# BT100_V1_1.net
KiCad netlist of a schematic drawn in Altium Designer
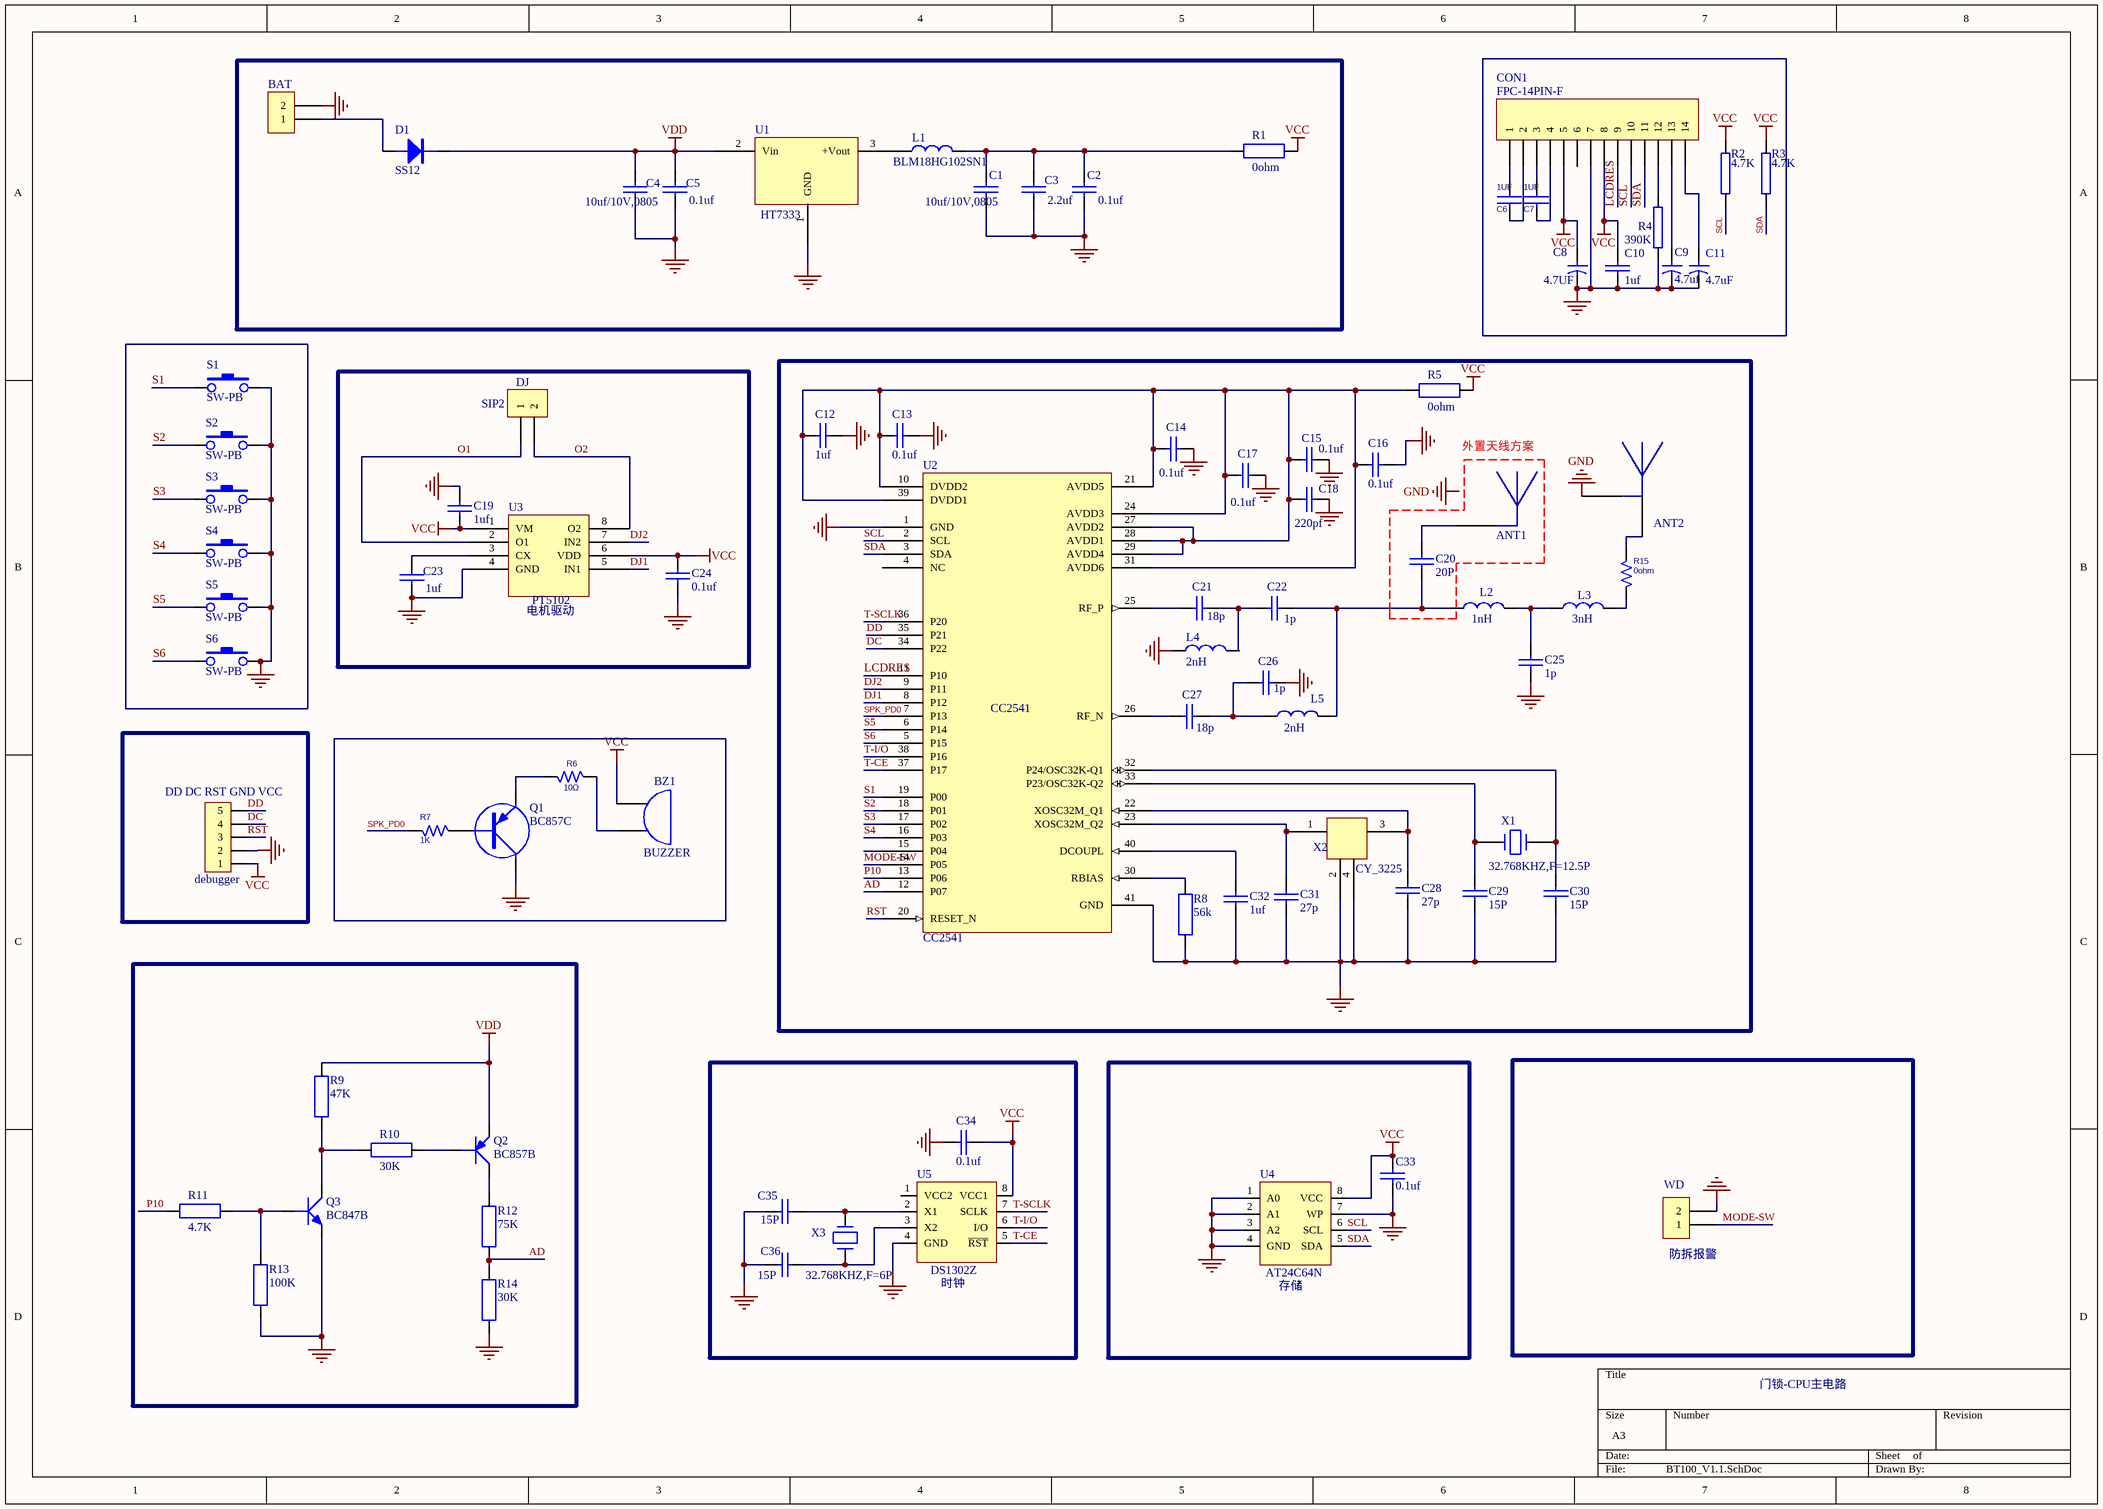
[diagram p0: BT100_V1.1.SchDoc]

(export (version "E")
  (design (tool "Eeschema 10.0.6"))
  (components
    (comp (ref "ANT1") (value "ANT") (footprint "IPEX") (libsource (lib "BT100_Project") (part "ANT1")))
    (comp (ref "ANT2") (value "ANT") (footprint "ANT") (libsource (lib "BT100_Project") (part "ANT")))
    (comp (ref "BAT")
      (value "CN1")
      (footprint "2PAD-9")
      (description "Connector")
      (libsource (lib "") (part "CON2_1"))
    )
    (comp (ref "BZ1")
      (value "BUZZER")
      (footprint "2PAD-9")
      (description "Buzzer")
      (libsource (lib "LG_SCH") (part "BUZZER"))
    )
    (comp (ref "C1")
      (value "10uf/10V,0805")
      (footprint "门锁:PC5-*****-**-0A_0805_TDK")
      (description "PC7-*****-KQA0A")
      (libsource (lib "Schlib") (part "PC7_0402_YAGEO"))
    )
    (comp (ref "C2")
      (value "0.1uf")
      (footprint "门锁:PC5-*****-**-0A_0603_TDK")
      (description "PC7-*****-KQA0A")
      (libsource (lib "Schlib") (part "PC7_0402_YAGEO"))
    )
    (comp (ref "C3")
      (value "2.2uf")
      (footprint "门锁:PC5-*****-**-0A_0603_TDK")
      (description "PC7-*****-KQA0A")
      (libsource (lib "Schlib") (part "PC7_0402_YAGEO"))
    )
    (comp (ref "C4")
      (value "10uf/10V,0805")
      (footprint "门锁:PC5-*****-**-0A_0805_TDK")
      (description "PC7-*****-KQA0A")
      (libsource (lib "Schlib") (part "PC7_0402_YAGEO"))
    )
    (comp (ref "C5")
      (value "0.1uf")
      (footprint "门锁:PC5-*****-**-0A_0603_TDK")
      (description "PC7-*****-KQA0A")
      (libsource (lib "Schlib") (part "PC7_0402_YAGEO"))
    )
    (comp (ref "C6") (value "1UF") (footprint "0603") (libsource (lib "*") (part "CAP NP_Dup3")))
    (comp (ref "C7") (value "1UF") (footprint "0603") (libsource (lib "*") (part "CAP NP_Dup3")))
    (comp (ref "C8")
      (value "4.7UF")
      (footprint "3216C")
      (description "1206")
      (libsource (lib "*") (part "CAP_E"))
    )
    (comp (ref "C9")
      (value "4.7uf")
      (footprint "3216C")
      (description "1206")
      (libsource (lib "*") (part "CAP_E"))
    )
    (comp (ref "C10")
      (value "1uf")
      (footprint "0603")
      (description "Capacitor")
      (libsource (lib "*") (part "CAP"))
    )
    (comp (ref "C11")
      (value "4.7uF")
      (footprint "3216C")
      (description "1206")
      (libsource (lib "*") (part "CAP_E"))
    )
    (comp (ref "C12")
      (value "1uf")
      (footprint "PC5-*****-**-0A_0603_TDK")
      (description "PC7-*****-KQA0A")
      (libsource (lib "Schlib") (part "PC7_0402_YAGEO"))
    )
    (comp (ref "C13")
      (value "0.1uf")
      (footprint "PC7-*****-KO-0A_0603_TDK")
      (description "PC7-*****-KQA0A")
      (libsource (lib "Schlib") (part "PC7_0402_YAGEO"))
    )
    (comp (ref "C14")
      (value "0.1uf")
      (footprint "PC5-*****-**-0A_0603_TDK")
      (description "PC7-*****-KQA0A")
      (libsource (lib "Schlib") (part "PC7_0402_YAGEO"))
    )
    (comp (ref "C15")
      (value "0.1uf")
      (footprint "PC7-*****-KQA0A_0402_YAGEO")
      (description "PC7-*****-KQA0A")
      (libsource (lib "Schlib") (part "PC7_0402_YAGEO"))
    )
    (comp (ref "C16")
      (value "0.1uf")
      (footprint "PC7-*****-KQA0A_0402_YAGEO")
      (description "PC7-*****-KQA0A")
      (libsource (lib "Schlib") (part "PC7_0402_YAGEO"))
    )
    (comp (ref "C17")
      (value "0.1uf")
      (footprint "PC7-*****-KQA0A_0402_YAGEO")
      (description "PC7-*****-KQA0A")
      (libsource (lib "Schlib") (part "PC7_0402_YAGEO"))
    )
    (comp (ref "C18")
      (value "220pf")
      (footprint "PC7-*****-KQA0A_0402_YAGEO")
      (description "PC7-*****-KQA0A")
      (libsource (lib "Schlib") (part "PC7_0402_YAGEO"))
    )
    (comp (ref "C19")
      (value "1uf")
      (footprint "门锁:PC5-*****-**-0A_0603_TDK")
      (description "PC7-*****-KQA0A")
      (libsource (lib "Schlib") (part "PC7_0402_YAGEO"))
    )
    (comp (ref "C20")
      (value "20P")
      (footprint "PC7-*****-KQA0A_0402_YAGEO")
      (description "PC7-*****-KQA0A")
      (libsource (lib "Schlib") (part "PC7_0402_YAGEO"))
    )
    (comp (ref "C21")
      (value "18p")
      (footprint "PC7-*****-KQA0A_0402_YAGEO")
      (description "PC7-*****-KQA0A")
      (libsource (lib "Schlib") (part "PC7_0402_YAGEO"))
    )
    (comp (ref "C22")
      (value "1p")
      (footprint "PC7-*****-KQA0A_0402_YAGEO")
      (description "PC7-*****-KQA0A")
      (libsource (lib "Schlib") (part "PC7_0402_YAGEO"))
    )
    (comp (ref "C23")
      (value "1uf")
      (footprint "门锁:PC5-*****-**-0A_0603_TDK")
      (description "PC7-*****-KQA0A")
      (libsource (lib "Schlib") (part "PC7_0402_YAGEO"))
    )
    (comp (ref "C24")
      (value "0.1uf")
      (footprint "门锁:PC5-*****-**-0A_0603_TDK")
      (description "PC7-*****-KQA0A")
      (libsource (lib "Schlib") (part "PC7_0402_YAGEO"))
    )
    (comp (ref "C25")
      (value "1p")
      (footprint "PC7-*****-KQA0A_0402_YAGEO")
      (description "PC7-*****-KQA0A")
      (libsource (lib "Schlib") (part "PC7_0402_YAGEO"))
    )
    (comp (ref "C26")
      (value "1p")
      (footprint "PC7-*****-KQA0A_0402_YAGEO")
      (description "PC7-*****-KQA0A")
      (libsource (lib "Schlib") (part "PC7_0402_YAGEO"))
    )
    (comp (ref "C27")
      (value "18p")
      (footprint "PC7-*****-KQA0A_0402_YAGEO")
      (description "PC7-*****-KQA0A")
      (libsource (lib "Schlib") (part "PC7_0402_YAGEO"))
    )
    (comp (ref "C28")
      (value "27p")
      (footprint "PC7-*****-KO-0A_0603_TDK")
      (description "PC7-*****-KQA0A")
      (libsource (lib "Schlib") (part "PC7_0402_YAGEO"))
    )
    (comp (ref "C29")
      (value "15P")
      (footprint "PC5-*****-**-0A_0603_TDK")
      (description "PC7-*****-KQA0A")
      (libsource (lib "Schlib") (part "PC7_0402_YAGEO"))
    )
    (comp (ref "C30")
      (value "15P")
      (footprint "PC7-*****-KO-0A_0603_TDK")
      (description "PC7-*****-KQA0A")
      (libsource (lib "Schlib") (part "PC7_0402_YAGEO"))
    )
    (comp (ref "C31")
      (value "27p")
      (footprint "PC7-*****-KO-0A_0603_TDK")
      (description "PC7-*****-KQA0A")
      (libsource (lib "Schlib") (part "PC7_0402_YAGEO"))
    )
    (comp (ref "C32")
      (value "1uf")
      (footprint "PC5-*****-**-0A_0603_TDK")
      (description "PC7-*****-KQA0A")
      (libsource (lib "Schlib") (part "PC7_0402_YAGEO"))
    )
    (comp (ref "C33")
      (value "0.1uf")
      (footprint "PC5-*****-**-0A_0603_TDK")
      (description "PC7-*****-KQA0A")
      (libsource (lib "Schlib") (part "PC7_0402_YAGEO"))
    )
    (comp (ref "C34")
      (value "0.1uf")
      (footprint "PC7-*****-KO-0A_0603_TDK")
      (description "PC7-*****-KQA0A")
      (libsource (lib "Schlib") (part "PC7_0402_YAGEO"))
    )
    (comp (ref "C35")
      (value "15P")
      (footprint "PC7-*****-KO-0A_0603_TDK")
      (description "PC7-*****-KQA0A")
      (libsource (lib "Schlib") (part "PC7_0402_YAGEO"))
    )
    (comp (ref "C36")
      (value "15P")
      (footprint "PC7-*****-KO-0A_0603_TDK")
      (description "PC7-*****-KQA0A")
      (libsource (lib "Schlib") (part "PC7_0402_YAGEO"))
    )
    (comp (ref "CON1")
      (value "FPC-14PIN-F")
      (footprint "FFC6214")
      (description "Connector")
      (libsource (lib "*") (part "CON14"))
    )
    (comp (ref "D1")
      (value "SS12")
      (footprint "SS12-DIDEO")
      (description "PDD-00330-00-2A")
      (libsource (lib "*") (part "PDD_SD101CWS"))
    )
    (comp (ref "DD DC RST GND VCC")
      (value "debugger")
      (footprint "ISCP-5PIN")
      (libsource (lib "BJC") (part "CON5"))
    )
    (comp (ref "DJ")
      (value "SIP2")
      (footprint "2PAD-9")
      (description "Connector")
      (libsource (lib "BJC") (part "CON2"))
    )
    (comp (ref "L1")
      (value "BLM18HG102SN1")
      (footprint "门锁:PC5-*****-**-0A_0603_TDK")
      (description "PWL-00195-00-20")
      (libsource (lib "Schlib") (part "PWL_18nH"))
    )
    (comp (ref "L2")
      (value "1nH")
      (footprint "PC5-*****-**-0A_0402_TDK")
      (description "PWL-00195-00-20")
      (libsource (lib "Schlib") (part "PWL_18nH"))
    )
    (comp (ref "L3")
      (value "3nH")
      (footprint "PC5-*****-**-0A_0402_TDK")
      (description "PWL-00195-00-20")
      (libsource (lib "Schlib") (part "PWL_18nH"))
    )
    (comp (ref "L4")
      (value "2nH")
      (footprint "PC5-*****-**-0A_0402_TDK")
      (description "PWL-00195-00-20")
      (libsource (lib "Schlib") (part "PWL_18nH"))
    )
    (comp (ref "L5")
      (value "2nH")
      (footprint "PC5-*****-**-0A_0402_TDK")
      (description "PWL-00195-00-20")
      (libsource (lib "Schlib") (part "PWL_18nH"))
    )
    (comp (ref "Q1")
      (value "BC857C")
      (footprint "PTR-C0025-00-2A_2SC1623")
      (description "PNP Transistor")
      (libsource (lib "LG_SCH") (part "PNP"))
    )
    (comp (ref "Q2")
      (value "BC857B")
      (footprint "PTR-C0025-00-2A_2SC1623")
      (libsource (lib "*") (part "PTR-PNP"))
    )
    (comp (ref "Q3")
      (value "BC847B")
      (footprint "PTR-C0025-00-2A_2SC1623")
      (description "PTR-C0028-00-2A")
      (libsource (lib "Schlib") (part "PTR_2SC3356"))
    )
    (comp (ref "R1")
      (value "0ohm")
      (footprint "门锁:PC5-*****-**-0A_0603_TDK")
      (description "PRC-*****-AM-0A_0603")
      (libsource (lib "Schlib") (part "PRC_0603"))
    )
    (comp (ref "R2") (value "4.7K") (footprint "0603") (libsource (lib "LG_SCH") (part "RES")))
    (comp (ref "R3") (value "4.7K") (footprint "0603") (libsource (lib "LG_SCH") (part "RES")))
    (comp (ref "R4") (value "390K") (footprint "0603") (libsource (lib "LG_SCH") (part "RES")))
    (comp (ref "R5")
      (value "0ohm")
      (footprint "PRC-*****-AM-0A_0603")
      (description "PRC-*****-AM-0A_0603")
      (libsource (lib "Schlib") (part "PRC_0603"))
    )
    (comp (ref "R6") (value "10Ω") (footprint "0603") (libsource (lib "*") (part "R_Dup3")))
    (comp (ref "R7") (value "1K") (footprint "0603") (libsource (lib "*") (part "R_Dup3")))
    (comp (ref "R8")
      (value "56k")
      (footprint "PRC-*****-BM-0A_0402")
      (description "PRC-*****-AM-0A_0603")
      (libsource (lib "Schlib") (part "PRC_0603"))
    )
    (comp (ref "R9")
      (value "47K")
      (footprint "门锁:PC7-*****-KO-0A_0603_TDK")
      (description "PRC-*****-AM-0A_0603")
      (libsource (lib "Schlib") (part "PRC_0603"))
    )
    (comp (ref "R10")
      (value "30K")
      (footprint "门锁:PC5-*****-**-0A_0603_TDK")
      (description "PRC-*****-AM-0A_0603")
      (libsource (lib "Schlib") (part "PRC_0603"))
    )
    (comp (ref "R11")
      (value "4.7K")
      (footprint "门锁:PC5-*****-**-0A_0603_TDK")
      (description "PRC-*****-AM-0A_0603")
      (libsource (lib "Schlib") (part "PRC_0603"))
    )
    (comp (ref "R12")
      (value "75K")
      (footprint "门锁:PC5-*****-**-0A_0603_TDK")
      (description "PRC-*****-AM-0A_0603")
      (libsource (lib "Schlib") (part "PRC_0603"))
    )
    (comp (ref "R13")
      (value "100K")
      (footprint "门锁:PC5-*****-**-0A_0603_TDK")
      (description "PRC-*****-AM-0A_0603")
      (libsource (lib "Schlib") (part "PRC_0603"))
    )
    (comp (ref "R14")
      (value "30K")
      (footprint "门锁:PC5-*****-**-0A_0603_TDK")
      (description "PRC-*****-AM-0A_0603")
      (libsource (lib "Schlib") (part "PRC_0603"))
    )
    (comp (ref "R15")
      (value "0ohm")
      (footprint "PC7-*****-KQA0A_0402_YAGEO")
      (libsource (lib "*") (part "R_Dup3"))
    )
    (comp (ref "S1") (value "SW-PB") (footprint "TS-030") (libsource (lib "LG_SCH") (part "SW-PB")))
    (comp (ref "S2") (value "SW-PB") (footprint "TS-030") (libsource (lib "LG_SCH") (part "SW-PB")))
    (comp (ref "S3") (value "SW-PB") (footprint "TS-030") (libsource (lib "LG_SCH") (part "SW-PB")))
    (comp (ref "S4") (value "SW-PB") (footprint "TS-030") (libsource (lib "LG_SCH") (part "SW-PB")))
    (comp (ref "S5") (value "SW-PB") (footprint "TS-030") (libsource (lib "LG_SCH") (part "SW-PB")))
    (comp (ref "S6") (value "SW-PB") (footprint "TS-030") (libsource (lib "LG_SCH") (part "SW-PB")))
    (comp (ref "U1") (value "HT7333") (footprint "SOT89") (libsource (lib "*") (part "LM117K")))
    (comp (ref "U2") (value "CC2541") (footprint "CC2530_QFN40") (libsource (lib "*") (part "CC2541")))
    (comp (ref "U3") (value "PT5102") (footprint "PT5102") (libsource (lib "BJC") (part "Component_1_1")))
    (comp (ref "U4")
      (value "AT24C64N")
      (footprint "PIC-00570-40-2A_93LC46B")
      (libsource (lib "BJC") (part "AT24C64N"))
    )
    (comp (ref "U5")
      (value "DS1302Z")
      (footprint "PIC-00570-40-2A_93LC46B")
      (libsource (lib "BJC") (part "DS1302"))
    )
    (comp (ref "WD")
      (value "CN1")
      (footprint "2PAD-9")
      (description "Connector")
      (libsource (lib "") (part "CON2_1"))
    )
    (comp (ref "X1")
      (value "32.768KHZ,F=12.5P")
      (footprint "FC-135")
      (description "Crystal")
      (libsource (lib "CC254xEM原理图库") (part "CRYSTAL"))
    )
    (comp (ref "X2")
      (value "CY_3225")
      (footprint "CY_3225")
      (libsource (lib "CC254xEM原理图库") (part "CY_3225"))
    )
    (comp (ref "X3")
      (value "32.768KHZ,F=6P")
      (footprint "门锁:FC-135")
      (description "PTR-X0320-20-2A")
      (libsource (lib "BJC") (part "PTR_16MHZ"))
    )
  )
  (nets
    (net (code "1") (name "/AD") (class "Default")
      (node (ref "R12") (pin "1") (pinfunction "1_1") (pintype "passive"))
      (node (ref "R14") (pin "2") (pinfunction "2_2") (pintype "passive"))
      (node (ref "U2") (pin "12") (pinfunction "P07_12") (pintype "passive"))
    )
    (net (code "2") (name "/DC") (class "Default")
      (node (ref "DD DC RST GND VCC") (pin "4") (pinfunction "4_4") (pintype "passive"))
      (node (ref "U2") (pin "34") (pinfunction "P22_34") (pintype "passive"))
    )
    (net (code "3") (name "/DD") (class "Default")
      (node (ref "DD DC RST GND VCC") (pin "5") (pinfunction "5_5") (pintype "passive"))
      (node (ref "U2") (pin "35") (pinfunction "P21_35") (pintype "passive"))
    )
    (net (code "4") (name "/DJ1") (class "Default")
      (node (ref "U2") (pin "8") (pinfunction "P12_8") (pintype "passive"))
      (node (ref "U3") (pin "5") (pinfunction "IN1_5") (pintype "passive"))
    )
    (net (code "5") (name "/DJ2") (class "Default")
      (node (ref "U2") (pin "9") (pinfunction "P11_9") (pintype "passive"))
      (node (ref "U3") (pin "7") (pinfunction "IN2_7") (pintype "passive"))
    )
    (net (code "6") (name "/LCDRES") (class "Default")
      (node (ref "CON1") (pin "9") (pinfunction "9_9") (pintype "passive"))
      (node (ref "U2") (pin "11") (pinfunction "P10_11") (pintype "passive"))
    )
    (net (code "7") (name "/MODE-SW") (class "Default")
      (node (ref "U2") (pin "14") (pinfunction "P05_14") (pintype "passive"))
      (node (ref "WD") (pin "1") (pinfunction "1_1") (pintype "passive"))
    )
    (net (code "8") (name "/O1") (class "Default")
      (node (ref "DJ") (pin "1") (pinfunction "1_1") (pintype "passive"))
      (node (ref "U3") (pin "2") (pinfunction "O1_2") (pintype "passive"))
    )
    (net (code "9") (name "/O2") (class "Default")
      (node (ref "DJ") (pin "2") (pinfunction "2_2") (pintype "passive"))
      (node (ref "U3") (pin "8") (pinfunction "O2_8") (pintype "passive"))
    )
    (net (code "10") (name "/P10") (class "Default")
      (node (ref "R11") (pin "1") (pinfunction "1_1") (pintype "passive"))
      (node (ref "U2") (pin "13") (pinfunction "P06_13") (pintype "passive"))
    )
    (net (code "11") (name "/RST") (class "Default")
      (node (ref "DD DC RST GND VCC") (pin "3") (pinfunction "3_3") (pintype "passive"))
      (node (ref "U2") (pin "20") (pinfunction "RESET_N_20") (pintype "input"))
    )
    (net (code "12") (name "/S1") (class "Default")
      (node (ref "S1") (pin "1") (pinfunction "1_1") (pintype "passive"))
      (node (ref "U2") (pin "19") (pinfunction "P00_19") (pintype "passive"))
    )
    (net (code "13") (name "/S2") (class "Default")
      (node (ref "S2") (pin "1") (pinfunction "1_1") (pintype "passive"))
      (node (ref "U2") (pin "18") (pinfunction "P01_18") (pintype "passive"))
    )
    (net (code "14") (name "/S3") (class "Default")
      (node (ref "S3") (pin "1") (pinfunction "1_1") (pintype "passive"))
      (node (ref "U2") (pin "17") (pinfunction "P02_17") (pintype "passive"))
    )
    (net (code "15") (name "/S4") (class "Default")
      (node (ref "S4") (pin "1") (pinfunction "1_1") (pintype "passive"))
      (node (ref "U2") (pin "16") (pinfunction "P03_16") (pintype "passive"))
    )
    (net (code "16") (name "/S5") (class "Default")
      (node (ref "S5") (pin "1") (pinfunction "1_1") (pintype "passive"))
      (node (ref "U2") (pin "6") (pinfunction "P14_6") (pintype "passive"))
    )
    (net (code "17") (name "/S6") (class "Default")
      (node (ref "S6") (pin "1") (pinfunction "1_1") (pintype "passive"))
      (node (ref "U2") (pin "5") (pinfunction "P15_5") (pintype "passive"))
    )
    (net (code "18") (name "/SCL") (class "Default")
      (node (ref "CON1") (pin "10") (pinfunction "10_10") (pintype "passive"))
      (node (ref "R2") (pin "1") (pinfunction "1_1") (pintype "passive"))
      (node (ref "U2") (pin "2") (pinfunction "SCL_2") (pintype "power_in"))
      (node (ref "U4") (pin "6") (pinfunction "SCL_6") (pintype "passive"))
    )
    (net (code "19") (name "/SDA") (class "Default")
      (node (ref "CON1") (pin "11") (pinfunction "11_11") (pintype "passive"))
      (node (ref "R3") (pin "1") (pinfunction "1_1") (pintype "passive"))
      (node (ref "U2") (pin "3") (pinfunction "SDA_3") (pintype "power_in"))
      (node (ref "U4") (pin "5") (pinfunction "SDA_5") (pintype "passive"))
    )
    (net (code "20") (name "/SPK_PD0") (class "Default")
      (node (ref "R7") (pin "1") (pinfunction "1_1") (pintype "passive"))
      (node (ref "U2") (pin "7") (pinfunction "P13_7") (pintype "passive"))
    )
    (net (code "21") (name "/T-CE") (class "Default")
      (node (ref "U2") (pin "37") (pinfunction "P17_37") (pintype "passive"))
      (node (ref "U5") (pin "5") (pinfunction "~{RST}_5") (pintype "passive"))
    )
    (net (code "22") (name "/T-I{slash}O") (class "Default")
      (node (ref "U2") (pin "38") (pinfunction "P16_38") (pintype "passive"))
      (node (ref "U5") (pin "6") (pinfunction "I/O_6") (pintype "passive"))
    )
    (net (code "23") (name "/T-SCLK") (class "Default")
      (node (ref "U2") (pin "36") (pinfunction "P20_36") (pintype "passive"))
      (node (ref "U5") (pin "7") (pinfunction "SCLK_7") (pintype "passive"))
    )
    (net (code "24") (name "GND") (class "Default")
      (node (ref "ANT2") (pin "2") (pinfunction "2_2") (pintype "passive"))
      (node (ref "BAT") (pin "2") (pinfunction "2_2") (pintype "passive"))
      (node (ref "C1") (pin "1") (pinfunction "1_1") (pintype "passive"))
      (node (ref "C10") (pin "2") (pinfunction "2_2") (pintype "passive"))
      (node (ref "C11") (pin "2") (pinfunction "2_2") (pintype "passive"))
      (node (ref "C12") (pin "2") (pinfunction "2_2") (pintype "passive"))
      (node (ref "C13") (pin "2") (pinfunction "2_2") (pintype "passive"))
      (node (ref "C14") (pin "2") (pinfunction "2_2") (pintype "passive"))
      (node (ref "C15") (pin "2") (pinfunction "2_2") (pintype "passive"))
      (node (ref "C16") (pin "2") (pinfunction "2_2") (pintype "passive"))
      (node (ref "C17") (pin "2") (pinfunction "2_2") (pintype "passive"))
      (node (ref "C18") (pin "1") (pinfunction "1_1") (pintype "passive"))
      (node (ref "C19") (pin "1") (pinfunction "1_1") (pintype "passive"))
      (node (ref "C2") (pin "1") (pinfunction "1_1") (pintype "passive"))
      (node (ref "C23") (pin "1") (pinfunction "1_1") (pintype "passive"))
      (node (ref "C24") (pin "1") (pinfunction "1_1") (pintype "passive"))
      (node (ref "C25") (pin "1") (pinfunction "1_1") (pintype "passive"))
      (node (ref "C26") (pin "2") (pinfunction "2_2") (pintype "passive"))
      (node (ref "C28") (pin "1") (pinfunction "1_1") (pintype "passive"))
      (node (ref "C29") (pin "1") (pinfunction "1_1") (pintype "passive"))
      (node (ref "C3") (pin "2") (pinfunction "2_2") (pintype "passive"))
      (node (ref "C30") (pin "1") (pinfunction "1_1") (pintype "passive"))
      (node (ref "C31") (pin "1") (pinfunction "1_1") (pintype "passive"))
      (node (ref "C32") (pin "1") (pinfunction "1_1") (pintype "passive"))
      (node (ref "C33") (pin "1") (pinfunction "1_1") (pintype "passive"))
      (node (ref "C34") (pin "2") (pinfunction "2_2") (pintype "passive"))
      (node (ref "C35") (pin "2") (pinfunction "2_2") (pintype "passive"))
      (node (ref "C36") (pin "2") (pinfunction "2_2") (pintype "passive"))
      (node (ref "C4") (pin "1") (pinfunction "1_1") (pintype "passive"))
      (node (ref "C5") (pin "1") (pinfunction "1_1") (pintype "passive"))
      (node (ref "C8") (pin "2") (pinfunction "2_2") (pintype "passive"))
      (node (ref "C9") (pin "2") (pinfunction "2_2") (pintype "passive"))
      (node (ref "CON1") (pin "7") (pinfunction "7_7") (pintype "passive"))
      (node (ref "DD DC RST GND VCC") (pin "2") (pinfunction "2_2") (pintype "passive"))
      (node (ref "L4") (pin "1") (pintype "passive"))
      (node (ref "Q1") (pin "C") (pinfunction "C_C") (pintype "passive"))
      (node (ref "Q3") (pin "E") (pinfunction "1_E") (pintype "passive"))
      (node (ref "R13") (pin "1") (pinfunction "1_1") (pintype "passive"))
      (node (ref "R14") (pin "1") (pinfunction "1_1") (pintype "passive"))
      (node (ref "R4") (pin "1") (pinfunction "1_1") (pintype "passive"))
      (node (ref "R8") (pin "2") (pinfunction "2_2") (pintype "passive"))
      (node (ref "S1") (pin "2") (pinfunction "2_2") (pintype "passive"))
      (node (ref "S2") (pin "2") (pinfunction "2_2") (pintype "passive"))
      (node (ref "S3") (pin "2") (pinfunction "2_2") (pintype "passive"))
      (node (ref "S4") (pin "2") (pinfunction "2_2") (pintype "passive"))
      (node (ref "S5") (pin "2") (pinfunction "2_2") (pintype "passive"))
      (node (ref "S6") (pin "2") (pinfunction "2_2") (pintype "passive"))
      (node (ref "U1") (pin "1") (pinfunction "GND_1") (pintype "passive"))
      (node (ref "U2") (pin "1") (pinfunction "GND_1") (pintype "power_in"))
      (node (ref "U2") (pin "41") (pinfunction "GND_41") (pintype "power_in"))
      (node (ref "U3") (pin "4") (pinfunction "GND_4") (pintype "passive"))
      (node (ref "U4") (pin "1") (pinfunction "A0_1") (pintype "passive"))
      (node (ref "U4") (pin "2") (pinfunction "A1_2") (pintype "passive"))
      (node (ref "U4") (pin "3") (pinfunction "A2_3") (pintype "passive"))
      (node (ref "U4") (pin "4") (pinfunction "GND_4") (pintype "passive"))
      (node (ref "U4") (pin "7") (pinfunction "WP_7") (pintype "passive"))
      (node (ref "U5") (pin "4") (pinfunction "GND_4") (pintype "passive"))
      (node (ref "WD") (pin "2") (pinfunction "2_2") (pintype "passive"))
      (node (ref "X2") (pin "2") (pinfunction "2_2") (pintype "power_in"))
      (node (ref "X2") (pin "4") (pinfunction "4_4") (pintype "power_in"))
    )
    (net (code "25") (name "Net-(ANT1-Pad2)") (class "Default")
      (node (ref "ANT1") (pin "2") (pinfunction "2_2") (pintype "passive"))
      (node (ref "C20") (pin "2") (pinfunction "2_2") (pintype "passive"))
    )
    (net (code "26") (name "Net-(ANT2-Pad1)") (class "Default")
      (node (ref "ANT2") (pin "1") (pinfunction "1_1") (pintype "passive"))
      (node (ref "R15") (pin "1") (pinfunction "1_1") (pintype "passive"))
    )
    (net (code "27") (name "Net-(BAT-Pad1)") (class "Default")
      (node (ref "BAT") (pin "1") (pinfunction "1_1") (pintype "passive"))
      (node (ref "D1") (pin "2") (pinfunction "2_2") (pintype "passive"))
    )
    (net (code "28") (name "Net-(BZ1-B)") (class "Default")
      (node (ref "BZ1") (pin "2") (pinfunction "B_2") (pintype "passive"))
      (node (ref "R6") (pin "2") (pinfunction "2_2") (pintype "passive"))
    )
    (net (code "29") (name "Net-(C1-Pad2)") (class "Default")
      (node (ref "C1") (pin "2") (pinfunction "2_2") (pintype "passive"))
      (node (ref "C2") (pin "2") (pinfunction "2_2") (pintype "passive"))
      (node (ref "C3") (pin "1") (pinfunction "1_1") (pintype "passive"))
      (node (ref "L1") (pin "2") (pintype "passive"))
      (node (ref "R1") (pin "1") (pinfunction "1_1") (pintype "passive"))
    )
    (net (code "30") (name "Net-(C6-Pad1)") (class "Default")
      (node (ref "C6") (pin "1") (pinfunction "1_1") (pintype "passive"))
      (node (ref "CON1") (pin "1") (pinfunction "1_1") (pintype "passive"))
    )
    (net (code "31") (name "Net-(C6-Pad2)") (class "Default")
      (node (ref "C6") (pin "2") (pinfunction "2_2") (pintype "passive"))
      (node (ref "CON1") (pin "2") (pinfunction "2_2") (pintype "passive"))
    )
    (net (code "32") (name "Net-(C7-Pad1)") (class "Default")
      (node (ref "C7") (pin "1") (pinfunction "1_1") (pintype "passive"))
      (node (ref "CON1") (pin "3") (pinfunction "3_3") (pintype "passive"))
    )
    (net (code "33") (name "Net-(C7-Pad2)") (class "Default")
      (node (ref "C7") (pin "2") (pinfunction "2_2") (pintype "passive"))
      (node (ref "CON1") (pin "4") (pinfunction "4_4") (pintype "passive"))
    )
    (net (code "34") (name "Net-(C9-Pad1)") (class "Default")
      (node (ref "C9") (pin "1") (pinfunction "1_1") (pintype "passive"))
      (node (ref "CON1") (pin "13") (pinfunction "13_13") (pintype "passive"))
    )
    (net (code "35") (name "Net-(C11-Pad1)") (class "Default")
      (node (ref "C11") (pin "1") (pinfunction "1_1") (pintype "passive"))
      (node (ref "CON1") (pin "14") (pinfunction "14_14") (pintype "passive"))
    )
    (net (code "36") (name "Net-(C20-Pad1)") (class "Default")
      (node (ref "C20") (pin "1") (pinfunction "1_1") (pintype "passive"))
      (node (ref "C22") (pin "2") (pinfunction "2_2") (pintype "passive"))
      (node (ref "L2") (pin "1") (pintype "passive"))
      (node (ref "L5") (pin "2") (pintype "passive"))
    )
    (net (code "37") (name "Net-(C21-Pad2)") (class "Default")
      (node (ref "C21") (pin "2") (pinfunction "2_2") (pintype "passive"))
      (node (ref "C22") (pin "1") (pinfunction "1_1") (pintype "passive"))
      (node (ref "L4") (pin "2") (pintype "passive"))
    )
    (net (code "38") (name "Net-(C25-Pad2)") (class "Default")
      (node (ref "C25") (pin "2") (pinfunction "2_2") (pintype "passive"))
      (node (ref "L2") (pin "2") (pintype "passive"))
      (node (ref "L3") (pin "1") (pintype "passive"))
    )
    (net (code "39") (name "Net-(C26-Pad1)") (class "Default")
      (node (ref "C26") (pin "1") (pinfunction "1_1") (pintype "passive"))
      (node (ref "C27") (pin "2") (pinfunction "2_2") (pintype "passive"))
      (node (ref "L5") (pin "1") (pintype "passive"))
    )
    (net (code "40") (name "Net-(CON1-Pad12)") (class "Default")
      (node (ref "CON1") (pin "12") (pinfunction "12_12") (pintype "passive"))
      (node (ref "R4") (pin "2") (pinfunction "2_2") (pintype "passive"))
    )
    (net (code "41") (name "Net-(D1-Pad1)") (class "Default")
      (node (ref "D1") (pin "1") (pinfunction "1_1") (pintype "passive"))
    )
    (net (code "42") (name "Net-(D1-Pad2)") (class "Default")
      (node (ref "D1") (pin "2") (pinfunction "2_2") (pintype "passive"))
    )
    (net (code "43") (name "Net-(L3-Pad2)") (class "Default")
      (node (ref "L3") (pin "2") (pintype "passive"))
      (node (ref "R15") (pin "2") (pinfunction "2_2") (pintype "passive"))
    )
    (net (code "44") (name "Net-(Q1-PadB)") (class "Default")
      (node (ref "Q1") (pin "B") (pinfunction "B_B") (pintype "passive"))
      (node (ref "R7") (pin "2") (pinfunction "2_2") (pintype "passive"))
    )
    (net (code "45") (name "Net-(Q1-PadE)") (class "Default")
      (node (ref "Q1") (pin "E") (pinfunction "E_E") (pintype "passive"))
      (node (ref "R6") (pin "1") (pinfunction "1_1") (pintype "passive"))
    )
    (net (code "46") (name "Net-(Q2-1)") (class "Default")
      (node (ref "Q2") (pin "B") (pinfunction "1_B") (pintype "passive"))
      (node (ref "R10") (pin "2") (pinfunction "2_2") (pintype "passive"))
    )
    (net (code "47") (name "Net-(Q2-3)") (class "Default")
      (node (ref "Q2") (pin "C") (pinfunction "3_C") (pintype "passive"))
      (node (ref "R12") (pin "2") (pinfunction "2_2") (pintype "passive"))
    )
    (net (code "48") (name "Net-(Q3-2)") (class "Default")
      (node (ref "Q3") (pin "B") (pinfunction "2_B") (pintype "passive"))
      (node (ref "R11") (pin "2") (pinfunction "2_2") (pintype "passive"))
      (node (ref "R13") (pin "2") (pinfunction "2_2") (pintype "passive"))
    )
    (net (code "49") (name "Net-(Q3-3)") (class "Default")
      (node (ref "Q3") (pin "C") (pinfunction "3_C") (pintype "passive"))
      (node (ref "R10") (pin "1") (pinfunction "1_1") (pintype "passive"))
      (node (ref "R9") (pin "1") (pinfunction "1_1") (pintype "passive"))
    )
    (net (code "50") (name "Net-(U1-+Vout)") (class "Default")
      (node (ref "L1") (pin "1") (pintype "passive"))
      (node (ref "U1") (pin "3") (pinfunction "+Vout_3") (pintype "passive"))
    )
    (net (code "51") (name "Net-(U2-AVDD1)") (class "Default")
      (node (ref "C12") (pin "1") (pinfunction "1_1") (pintype "passive"))
      (node (ref "C13") (pin "1") (pinfunction "1_1") (pintype "passive"))
      (node (ref "C14") (pin "1") (pinfunction "1_1") (pintype "passive"))
      (node (ref "C15") (pin "1") (pinfunction "1_1") (pintype "passive"))
      (node (ref "C16") (pin "1") (pinfunction "1_1") (pintype "passive"))
      (node (ref "C17") (pin "1") (pinfunction "1_1") (pintype "passive"))
      (node (ref "C18") (pin "2") (pinfunction "2_2") (pintype "passive"))
      (node (ref "R5") (pin "1") (pinfunction "1_1") (pintype "passive"))
      (node (ref "U2") (pin "10") (pinfunction "DVDD2_10") (pintype "power_in"))
      (node (ref "U2") (pin "21") (pinfunction "AVDD5_21") (pintype "power_in"))
      (node (ref "U2") (pin "24") (pinfunction "AVDD3_24") (pintype "power_in"))
      (node (ref "U2") (pin "27") (pinfunction "AVDD2_27") (pintype "power_in"))
      (node (ref "U2") (pin "28") (pinfunction "AVDD1_28") (pintype "power_in"))
      (node (ref "U2") (pin "29") (pinfunction "AVDD4_29") (pintype "power_in"))
      (node (ref "U2") (pin "31") (pinfunction "AVDD6_31") (pintype "power_in"))
      (node (ref "U2") (pin "39") (pinfunction "DVDD1_39") (pintype "power_in"))
    )
    (net (code "52") (name "Net-(U2-DCOUPL)") (class "Default")
      (node (ref "C32") (pin "2") (pinfunction "2_2") (pintype "passive"))
      (node (ref "U2") (pin "40") (pinfunction "DCOUPL_40") (pintype "input"))
    )
    (net (code "53") (name "Net-(U2-P23{slash}OSC32K-Q2)") (class "Default")
      (node (ref "C29") (pin "2") (pinfunction "2_2") (pintype "passive"))
      (node (ref "U2") (pin "33") (pinfunction "P23/OSC32K-Q2_33") (pintype "bidirectional"))
      (node (ref "X1") (pin "1") (pinfunction "1_1") (pintype "passive"))
    )
    (net (code "54") (name "Net-(U2-P24{slash}OSC32K-Q1)") (class "Default")
      (node (ref "C30") (pin "2") (pinfunction "2_2") (pintype "passive"))
      (node (ref "U2") (pin "32") (pinfunction "P24/OSC32K-Q1_32") (pintype "bidirectional"))
      (node (ref "X1") (pin "2") (pinfunction "2_2") (pintype "passive"))
    )
    (net (code "55") (name "Net-(U2-RBIAS)") (class "Default")
      (node (ref "R8") (pin "1") (pinfunction "1_1") (pintype "passive"))
      (node (ref "U2") (pin "30") (pinfunction "RBIAS_30") (pintype "input"))
    )
    (net (code "56") (name "Net-(U2-RF_N)") (class "Default")
      (node (ref "C27") (pin "1") (pinfunction "1_1") (pintype "passive"))
      (node (ref "U2") (pin "26") (pinfunction "RF_N_26") (pintype "output"))
    )
    (net (code "57") (name "Net-(U2-RF_P)") (class "Default")
      (node (ref "C21") (pin "1") (pinfunction "1_1") (pintype "passive"))
      (node (ref "U2") (pin "25") (pinfunction "RF_P_25") (pintype "output"))
    )
    (net (code "58") (name "Net-(U2-XOSC32M_Q1)") (class "Default")
      (node (ref "C28") (pin "2") (pinfunction "2_2") (pintype "passive"))
      (node (ref "U2") (pin "22") (pinfunction "XOSC32M_Q1_22") (pintype "input"))
      (node (ref "X2") (pin "3") (pinfunction "3_3") (pintype "power_in"))
    )
    (net (code "59") (name "Net-(U2-XOSC32M_Q2)") (class "Default")
      (node (ref "C31") (pin "2") (pinfunction "2_2") (pintype "passive"))
      (node (ref "U2") (pin "23") (pinfunction "XOSC32M_Q2_23") (pintype "input"))
      (node (ref "X2") (pin "1") (pinfunction "1_1") (pintype "power_in"))
    )
    (net (code "60") (name "Net-(U3-CX)") (class "Default")
      (node (ref "C23") (pin "2") (pinfunction "2_2") (pintype "passive"))
      (node (ref "U3") (pin "3") (pinfunction "CX_3") (pintype "passive"))
    )
    (net (code "61") (name "Net-(U5-X1)") (class "Default")
      (node (ref "C35") (pin "1") (pinfunction "1_1") (pintype "passive"))
      (node (ref "U5") (pin "2") (pinfunction "X1_2") (pintype "passive"))
      (node (ref "X3") (pin "2") (pinfunction "2_2") (pintype "passive"))
    )
    (net (code "62") (name "Net-(U5-X2)") (class "Default")
      (node (ref "C36") (pin "1") (pinfunction "1_1") (pintype "passive"))
      (node (ref "U5") (pin "3") (pinfunction "X2_3") (pintype "passive"))
      (node (ref "X3") (pin "1") (pinfunction "1_1") (pintype "passive"))
    )
    (net (code "63") (name "VCC") (class "Default")
      (node (ref "BZ1") (pin "1") (pinfunction "A_1") (pintype "passive"))
      (node (ref "C10") (pin "1") (pinfunction "1_1") (pintype "passive"))
      (node (ref "C19") (pin "2") (pinfunction "2_2") (pintype "passive"))
      (node (ref "C24") (pin "2") (pinfunction "2_2") (pintype "passive"))
      (node (ref "C33") (pin "2") (pinfunction "2_2") (pintype "passive"))
      (node (ref "C34") (pin "1") (pinfunction "1_1") (pintype "passive"))
      (node (ref "C8") (pin "1") (pinfunction "1_1") (pintype "passive"))
      (node (ref "CON1") (pin "5") (pinfunction "5_5") (pintype "passive"))
      (node (ref "CON1") (pin "8") (pinfunction "8_8") (pintype "passive"))
      (node (ref "DD DC RST GND VCC") (pin "1") (pinfunction "1_1") (pintype "passive"))
      (node (ref "R1") (pin "2") (pinfunction "2_2") (pintype "passive"))
      (node (ref "R2") (pin "2") (pinfunction "2_2") (pintype "passive"))
      (node (ref "R3") (pin "2") (pinfunction "2_2") (pintype "passive"))
      (node (ref "R5") (pin "2") (pinfunction "2_2") (pintype "passive"))
      (node (ref "U3") (pin "1") (pinfunction "VM_1") (pintype "passive"))
      (node (ref "U3") (pin "6") (pinfunction "VDD_6") (pintype "passive"))
      (node (ref "U4") (pin "8") (pinfunction "VCC_8") (pintype "passive"))
      (node (ref "U5") (pin "8") (pinfunction "VCC1_8") (pintype "passive"))
    )
    (net (code "64") (name "VDD") (class "Default")
      (node (ref "C4") (pin "2") (pinfunction "2_2") (pintype "passive"))
      (node (ref "C5") (pin "2") (pinfunction "2_2") (pintype "passive"))
      (node (ref "D1") (pin "1") (pinfunction "1_1") (pintype "passive"))
      (node (ref "Q2") (pin "E") (pinfunction "2_E") (pintype "passive"))
      (node (ref "R9") (pin "2") (pinfunction "2_2") (pintype "passive"))
      (node (ref "U1") (pin "2") (pinfunction "Vin_2") (pintype "passive"))
    )
    (net (code "65") (name "unconnected-(CON1-Pad6)") (class "Default")
      (node (ref "CON1") (pin "6") (pinfunction "6_6") (pintype "passive"))
    )
    (net (code "66") (name "unconnected-(U2-NC-Pad4)") (class "Default")
      (node (ref "U2") (pin "4") (pinfunction "NC_4") (pintype "power_in"))
    )
    (net (code "67") (name "unconnected-(U2-P04-Pad15)") (class "Default")
      (node (ref "U2") (pin "15") (pinfunction "P04_15") (pintype "passive"))
    )
    (net (code "68") (name "unconnected-(U5-VCC2-Pad1)") (class "Default")
      (node (ref "U5") (pin "1") (pinfunction "VCC2_1") (pintype "passive"))
    )
  )
)
